# Pallette_v0_5.net
KiCad netlist of a schematic drawn in Altium Designer
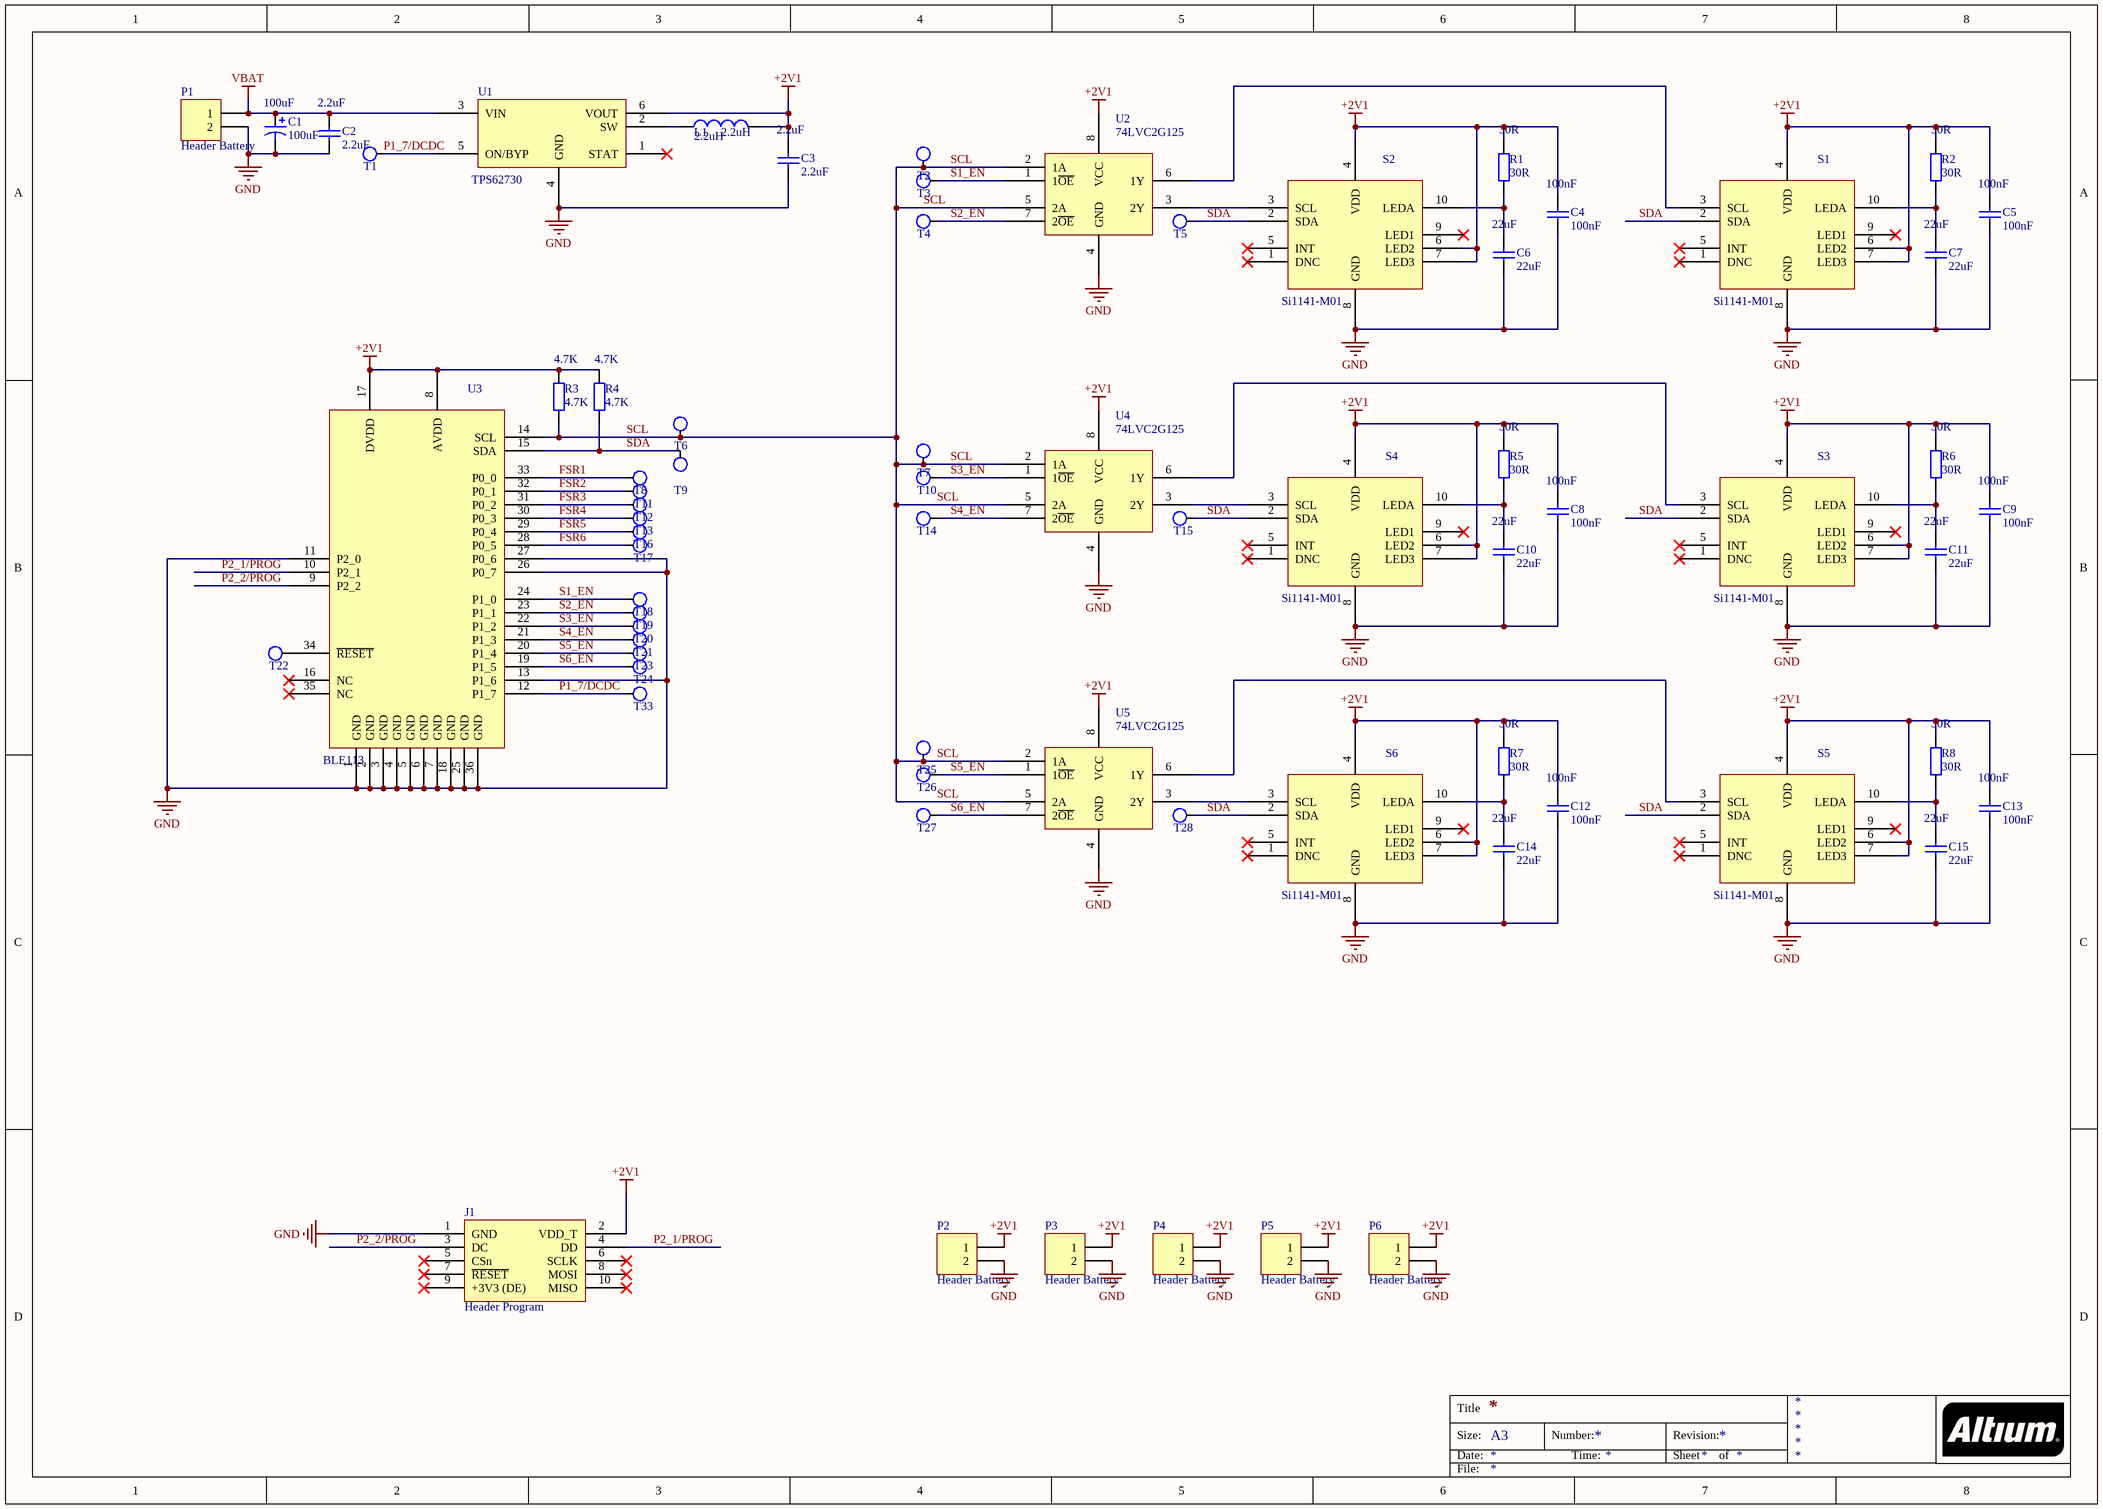
[diagram p0: Pallette v0.5.SchDoc]

(export (version "E")
  (design (tool "Eeschema 10.0.6"))
  (components
    (comp (ref "C1")
      (value "100uF")
      (footprint "1411")
      (description "CAP TANT POLY 100UF 8V 1411")
      (fields
        (field (name "ALTIUM_VALUE") "100uF")
        (field (name "DIGI-KEY PART NUMBER") "P16641CT-ND")
        (field (name "MANUFACTURER") "Panasonic Electronic Components")
      )
      (libsource (lib "Schlib") (part "Cap Pol 100uF"))
    )
    (comp (ref "C2")
      (value "2.2uF")
      (footprint "0402")
      (description "CAP CER 2.2UF 6.3V X5R 0402")
      (fields
        (field (name "ALTIUM_VALUE") "2.2uF")
        (field (name "DIGI-KEY PART NUMBER") "478-7885-1-ND")
        (field (name "MANUFACTURER PART NUMBER") "04026D225KAT2A")
      )
      (libsource (lib "Schlib") (part "Cap 2.2uF"))
    )
    (comp (ref "C3")
      (value "2.2uF")
      (footprint "0402")
      (description "CAP CER 2.2UF 6.3V X5R 0402")
      (fields
        (field (name "ALTIUM_VALUE") "2.2uF")
        (field (name "DIGI-KEY PART NUMBER") "478-7885-1-ND")
        (field (name "MANUFACTURER PART NUMBER") "04026D225KAT2A")
      )
      (libsource (lib "Schlib") (part "Cap 2.2uF"))
    )
    (comp (ref "C4")
      (value "100nF")
      (footprint "0402")
      (description "CAP CER 0.1UF 10V X5R 0402")
      (fields
        (field (name "ALTIUM_VALUE") "100nF")
        (field (name "DIGI-KEY PART NUMBER") "490-1318-1-ND")
        (field (name "MANUFACTURER") "Murata")
      )
      (libsource (lib "Schlib") (part "Cap 100nF"))
    )
    (comp (ref "C5")
      (value "100nF")
      (footprint "0402")
      (description "CAP CER 0.1UF 10V X5R 0402")
      (fields
        (field (name "ALTIUM_VALUE") "100nF")
        (field (name "DIGI-KEY PART NUMBER") "490-1318-1-ND")
        (field (name "MANUFACTURER") "Murata")
      )
      (libsource (lib "Schlib") (part "Cap 100nF"))
    )
    (comp (ref "C6")
      (value "22uF")
      (footprint "0603")
      (description "CAP CER 22UF 6.3V X5R 0603")
      (fields
        (field (name "ALTIUM_VALUE") "22uF")
        (field (name "DIGI-KEY PART NUMBER") "490-7611-1-ND")
        (field (name "MANUFACTURER PART NUMBER") "GRM188R60J226MEA0D")
      )
      (libsource (lib "Schlib") (part "Cap 22uF"))
    )
    (comp (ref "C7")
      (value "22uF")
      (footprint "0603")
      (description "CAP CER 22UF 6.3V X5R 0603")
      (fields
        (field (name "ALTIUM_VALUE") "22uF")
        (field (name "DIGI-KEY PART NUMBER") "490-7611-1-ND")
        (field (name "MANUFACTURER PART NUMBER") "GRM188R60J226MEA0D")
      )
      (libsource (lib "Schlib") (part "Cap 22uF"))
    )
    (comp (ref "C8")
      (value "100nF")
      (footprint "0402")
      (description "CAP CER 0.1UF 10V X5R 0402")
      (fields
        (field (name "ALTIUM_VALUE") "100nF")
        (field (name "DIGI-KEY PART NUMBER") "490-1318-1-ND")
        (field (name "MANUFACTURER") "Murata")
      )
      (libsource (lib "Schlib") (part "Cap 100nF"))
    )
    (comp (ref "C9")
      (value "100nF")
      (footprint "0402")
      (description "CAP CER 0.1UF 10V X5R 0402")
      (fields
        (field (name "ALTIUM_VALUE") "100nF")
        (field (name "DIGI-KEY PART NUMBER") "490-1318-1-ND")
        (field (name "MANUFACTURER") "Murata")
      )
      (libsource (lib "Schlib") (part "Cap 100nF"))
    )
    (comp (ref "C10")
      (value "22uF")
      (footprint "0603")
      (description "CAP CER 22UF 6.3V X5R 0603")
      (fields
        (field (name "ALTIUM_VALUE") "22uF")
        (field (name "DIGI-KEY PART NUMBER") "490-7611-1-ND")
        (field (name "MANUFACTURER PART NUMBER") "GRM188R60J226MEA0D")
      )
      (libsource (lib "Schlib") (part "Cap 22uF"))
    )
    (comp (ref "C11")
      (value "22uF")
      (footprint "0603")
      (description "CAP CER 22UF 6.3V X5R 0603")
      (fields
        (field (name "ALTIUM_VALUE") "22uF")
        (field (name "DIGI-KEY PART NUMBER") "490-7611-1-ND")
        (field (name "MANUFACTURER PART NUMBER") "GRM188R60J226MEA0D")
      )
      (libsource (lib "Schlib") (part "Cap 22uF"))
    )
    (comp (ref "C12")
      (value "100nF")
      (footprint "0402")
      (description "CAP CER 0.1UF 10V X5R 0402")
      (fields
        (field (name "ALTIUM_VALUE") "100nF")
        (field (name "DIGI-KEY PART NUMBER") "490-1318-1-ND")
        (field (name "MANUFACTURER") "Murata")
      )
      (libsource (lib "Schlib") (part "Cap 100nF"))
    )
    (comp (ref "C13")
      (value "100nF")
      (footprint "0402")
      (description "CAP CER 0.1UF 10V X5R 0402")
      (fields
        (field (name "ALTIUM_VALUE") "100nF")
        (field (name "DIGI-KEY PART NUMBER") "490-1318-1-ND")
        (field (name "MANUFACTURER") "Murata")
      )
      (libsource (lib "Schlib") (part "Cap 100nF"))
    )
    (comp (ref "C14")
      (value "22uF")
      (footprint "0603")
      (description "CAP CER 22UF 6.3V X5R 0603")
      (fields
        (field (name "ALTIUM_VALUE") "22uF")
        (field (name "DIGI-KEY PART NUMBER") "490-7611-1-ND")
        (field (name "MANUFACTURER PART NUMBER") "GRM188R60J226MEA0D")
      )
      (libsource (lib "Schlib") (part "Cap 22uF"))
    )
    (comp (ref "C15")
      (value "22uF")
      (footprint "0603")
      (description "CAP CER 22UF 6.3V X5R 0603")
      (fields
        (field (name "ALTIUM_VALUE") "22uF")
        (field (name "DIGI-KEY PART NUMBER") "490-7611-1-ND")
        (field (name "MANUFACTURER PART NUMBER") "GRM188R60J226MEA0D")
      )
      (libsource (lib "Schlib") (part "Cap 22uF"))
    )
    (comp (ref "J1")
      (value "Header Program")
      (footprint "TC2050-IDC-NL")
      (description "PADS PROGRAMMING")
      (libsource (lib "Schlib") (part "Header Program"))
    )
    (comp (ref "L1")
      (value "2.2uH")
      (footprint "0805")
      (description "FIXED IND 2.2UH 800MA 120 MOHM")
      (fields
        (field (name "ALTIUM_VALUE") "2.2uH")
        (field (name "DIGI-KEY PART NUMBER") "445-6758-1-ND")
        (field (name "MANUFACTURER") "TDK Corporation")
      )
      (libsource (lib "Schlib") (part "Ind 2.2uH"))
    )
    (comp (ref "P1")
      (value "Header Battery")
      (footprint "Battery Leads")
      (description "PADS BATTERY")
      (fields (field (name "PUBLISHER") "Altium Limited"))
      (libsource (lib "Schlib") (part "Header Battery"))
    )
    (comp (ref "P2")
      (value "Header Battery")
      (footprint "Battery Leads")
      (description "PADS BATTERY")
      (fields (field (name "PUBLISHER") "Altium Limited"))
      (libsource (lib "Schlib") (part "Header Battery"))
    )
    (comp (ref "P3")
      (value "Header Battery")
      (footprint "Battery Leads")
      (description "PADS BATTERY")
      (fields (field (name "PUBLISHER") "Altium Limited"))
      (libsource (lib "Schlib") (part "Header Battery"))
    )
    (comp (ref "P4")
      (value "Header Battery")
      (footprint "Battery Leads")
      (description "PADS BATTERY")
      (fields (field (name "PUBLISHER") "Altium Limited"))
      (libsource (lib "Schlib") (part "Header Battery"))
    )
    (comp (ref "P5")
      (value "Header Battery")
      (footprint "Battery Leads")
      (description "PADS BATTERY")
      (fields (field (name "PUBLISHER") "Altium Limited"))
      (libsource (lib "Schlib") (part "Header Battery"))
    )
    (comp (ref "P6")
      (value "Header Battery")
      (footprint "Battery Leads")
      (description "PADS BATTERY")
      (fields (field (name "PUBLISHER") "Altium Limited"))
      (libsource (lib "Schlib") (part "Header Battery"))
    )
    (comp (ref "R1")
      (value "30R")
      (footprint "0402")
      (description "RES SMD 30 OHM 1% 1/16W 0402")
      (fields
        (field (name "ALTIUM_VALUE") "30R")
        (field (name "DIGI-KEY PART NUMBER") "311-30LRCT-ND")
        (field (name "MANUFACTURER") "Yageo")
      )
      (libsource (lib "Schlib") (part "Res 30R"))
    )
    (comp (ref "R2")
      (value "30R")
      (footprint "0402")
      (description "RES SMD 30 OHM 1% 1/16W 0402")
      (fields
        (field (name "ALTIUM_VALUE") "30R")
        (field (name "DIGI-KEY PART NUMBER") "311-30LRCT-ND")
        (field (name "MANUFACTURER") "Yageo")
      )
      (libsource (lib "Schlib") (part "Res 30R"))
    )
    (comp (ref "R3")
      (value "4.7K")
      (footprint "0402")
      (description "RES SMD 4.7K OHM 1% 1/16W 0402")
      (fields
        (field (name "ALTIUM_VALUE") "4.7K")
        (field (name "DIGI-KEY PART NUMBER") "311-4.7KLRCT-ND")
        (field (name "MANUFACTURER") "Yageo")
      )
      (libsource (lib "Schlib") (part "Res 4.7K"))
    )
    (comp (ref "R4")
      (value "4.7K")
      (footprint "0402")
      (description "RES SMD 4.7K OHM 1% 1/16W 0402")
      (fields
        (field (name "ALTIUM_VALUE") "4.7K")
        (field (name "DIGI-KEY PART NUMBER") "311-4.7KLRCT-ND")
        (field (name "MANUFACTURER") "Yageo")
      )
      (libsource (lib "Schlib") (part "Res 4.7K"))
    )
    (comp (ref "R5")
      (value "30R")
      (footprint "0402")
      (description "RES SMD 30 OHM 1% 1/16W 0402")
      (fields
        (field (name "ALTIUM_VALUE") "30R")
        (field (name "DIGI-KEY PART NUMBER") "311-30LRCT-ND")
        (field (name "MANUFACTURER") "Yageo")
      )
      (libsource (lib "Schlib") (part "Res 30R"))
    )
    (comp (ref "R6")
      (value "30R")
      (footprint "0402")
      (description "RES SMD 30 OHM 1% 1/16W 0402")
      (fields
        (field (name "ALTIUM_VALUE") "30R")
        (field (name "DIGI-KEY PART NUMBER") "311-30LRCT-ND")
        (field (name "MANUFACTURER") "Yageo")
      )
      (libsource (lib "Schlib") (part "Res 30R"))
    )
    (comp (ref "R7")
      (value "30R")
      (footprint "0402")
      (description "RES SMD 30 OHM 1% 1/16W 0402")
      (fields
        (field (name "ALTIUM_VALUE") "30R")
        (field (name "DIGI-KEY PART NUMBER") "311-30LRCT-ND")
        (field (name "MANUFACTURER") "Yageo")
      )
      (libsource (lib "Schlib") (part "Res 30R"))
    )
    (comp (ref "R8")
      (value "30R")
      (footprint "0402")
      (description "RES SMD 30 OHM 1% 1/16W 0402")
      (fields
        (field (name "ALTIUM_VALUE") "30R")
        (field (name "DIGI-KEY PART NUMBER") "311-30LRCT-ND")
        (field (name "MANUFACTURER") "Yageo")
      )
      (libsource (lib "Schlib") (part "Res 30R"))
    )
    (comp (ref "S1")
      (value "Si1141-M01")
      (footprint "SI1141-M01")
      (description "SENSOR IR PROXIMITY AMB LT 10QFN")
      (fields
        (field (name "DIGI-KEY PART NUMBER") "336-3260-1-ND")
        (field (name "MANUFACTURER") "Silicon Labs")
      )
      (libsource (lib "Schlib") (part "Si1141-M01"))
    )
    (comp (ref "S2")
      (value "Si1141-M01")
      (footprint "SI1141-M01")
      (description "SENSOR IR PROXIMITY AMB LT 10QFN")
      (fields
        (field (name "DIGI-KEY PART NUMBER") "336-3260-1-ND")
        (field (name "MANUFACTURER") "Silicon Labs")
      )
      (libsource (lib "Schlib") (part "Si1141-M01"))
    )
    (comp (ref "S3")
      (value "Si1141-M01")
      (footprint "SI1141-M01")
      (description "SENSOR IR PROXIMITY AMB LT 10QFN")
      (fields
        (field (name "DIGI-KEY PART NUMBER") "336-3260-1-ND")
        (field (name "MANUFACTURER") "Silicon Labs")
      )
      (libsource (lib "Schlib") (part "Si1141-M01"))
    )
    (comp (ref "S4")
      (value "Si1141-M01")
      (footprint "SI1141-M01")
      (description "SENSOR IR PROXIMITY AMB LT 10QFN")
      (fields
        (field (name "DIGI-KEY PART NUMBER") "336-3260-1-ND")
        (field (name "MANUFACTURER") "Silicon Labs")
      )
      (libsource (lib "Schlib") (part "Si1141-M01"))
    )
    (comp (ref "S5")
      (value "Si1141-M01")
      (footprint "SI1141-M01")
      (description "SENSOR IR PROXIMITY AMB LT 10QFN")
      (fields
        (field (name "DIGI-KEY PART NUMBER") "336-3260-1-ND")
        (field (name "MANUFACTURER") "Silicon Labs")
      )
      (libsource (lib "Schlib") (part "Si1141-M01"))
    )
    (comp (ref "S6")
      (value "Si1141-M01")
      (footprint "SI1141-M01")
      (description "SENSOR IR PROXIMITY AMB LT 10QFN")
      (fields
        (field (name "DIGI-KEY PART NUMBER") "336-3260-1-ND")
        (field (name "MANUFACTURER") "Silicon Labs")
      )
      (libsource (lib "Schlib") (part "Si1141-M01"))
    )
    (comp (ref "T1")
      (value "TP 1.2X2MM")
      (footprint "TP 1.2x2MM")
      (description "TEST POINT")
      (libsource (lib "Schlib") (part "TP 1.2X2MM"))
    )
    (comp (ref "T2")
      (value "TP 1.2X2MM")
      (footprint "TP 1.2x2MM")
      (description "TEST POINT")
      (libsource (lib "Schlib") (part "TP 1.2X2MM"))
    )
    (comp (ref "T3")
      (value "TP 1.2X2MM")
      (footprint "TP 1.2x2MM")
      (description "TEST POINT")
      (libsource (lib "Schlib") (part "TP 1.2X2MM"))
    )
    (comp (ref "T4")
      (value "TP 1.2X2MM")
      (footprint "TP 1.2x2MM")
      (description "TEST POINT")
      (libsource (lib "Schlib") (part "TP 1.2X2MM"))
    )
    (comp (ref "T5")
      (value "TP 1.2X2MM")
      (footprint "TP 1.2x2MM")
      (description "TEST POINT")
      (libsource (lib "Schlib") (part "TP 1.2X2MM"))
    )
    (comp (ref "T6")
      (value "TP 1.2X2MM")
      (footprint "TP 1.2x2MM")
      (description "TEST POINT")
      (libsource (lib "Schlib") (part "TP 1.2X2MM"))
    )
    (comp (ref "T7")
      (value "TP 1.2X2MM")
      (footprint "TP 1.2x2MM")
      (description "TEST POINT")
      (libsource (lib "Schlib") (part "TP 1.2X2MM"))
    )
    (comp (ref "T8")
      (value "TP 1.2X2MM")
      (footprint "TP 1.2x2MM")
      (description "TEST POINT")
      (libsource (lib "Schlib") (part "TP 1.2X2MM"))
    )
    (comp (ref "T9")
      (value "TP 1.2X2MM")
      (footprint "TP 1.2x2MM")
      (description "TEST POINT")
      (libsource (lib "Schlib") (part "TP 1.2X2MM"))
    )
    (comp (ref "T10")
      (value "TP 1.2X2MM")
      (footprint "TP 1.2x2MM")
      (description "TEST POINT")
      (libsource (lib "Schlib") (part "TP 1.2X2MM"))
    )
    (comp (ref "T11")
      (value "TP 1.2X2MM")
      (footprint "TP 1.2x2MM")
      (description "TEST POINT")
      (libsource (lib "Schlib") (part "TP 1.2X2MM"))
    )
    (comp (ref "T12")
      (value "TP 1.2X2MM")
      (footprint "TP 1.2x2MM")
      (description "TEST POINT")
      (libsource (lib "Schlib") (part "TP 1.2X2MM"))
    )
    (comp (ref "T13")
      (value "TP 1.2X2MM")
      (footprint "TP 1.2x2MM")
      (description "TEST POINT")
      (libsource (lib "Schlib") (part "TP 1.2X2MM"))
    )
    (comp (ref "T14")
      (value "TP 1.2X2MM")
      (footprint "TP 1.2x2MM")
      (description "TEST POINT")
      (libsource (lib "Schlib") (part "TP 1.2X2MM"))
    )
    (comp (ref "T15")
      (value "TP 1.2X2MM")
      (footprint "TP 1.2x2MM")
      (description "TEST POINT")
      (libsource (lib "Schlib") (part "TP 1.2X2MM"))
    )
    (comp (ref "T16")
      (value "TP 1.2X2MM")
      (footprint "TP 1.2x2MM")
      (description "TEST POINT")
      (libsource (lib "Schlib") (part "TP 1.2X2MM"))
    )
    (comp (ref "T17")
      (value "TP 1.2X2MM")
      (footprint "TP 1.2x2MM")
      (description "TEST POINT")
      (libsource (lib "Schlib") (part "TP 1.2X2MM"))
    )
    (comp (ref "T18")
      (value "TP 1.2X2MM")
      (footprint "TP 1.2x2MM")
      (description "TEST POINT")
      (libsource (lib "Schlib") (part "TP 1.2X2MM"))
    )
    (comp (ref "T19")
      (value "TP 1.2X2MM")
      (footprint "TP 1.2x2MM")
      (description "TEST POINT")
      (libsource (lib "Schlib") (part "TP 1.2X2MM"))
    )
    (comp (ref "T20")
      (value "TP 1.2X2MM")
      (footprint "TP 1.2x2MM")
      (description "TEST POINT")
      (libsource (lib "Schlib") (part "TP 1.2X2MM"))
    )
    (comp (ref "T21")
      (value "TP 1.2X2MM")
      (footprint "TP 1.2x2MM")
      (description "TEST POINT")
      (libsource (lib "Schlib") (part "TP 1.2X2MM"))
    )
    (comp (ref "T22")
      (value "TP 1.2X2MM")
      (footprint "TP 1.2x2MM")
      (description "TEST POINT")
      (libsource (lib "Schlib") (part "TP 1.2X2MM"))
    )
    (comp (ref "T23")
      (value "TP 1.2X2MM")
      (footprint "TP 1.2x2MM")
      (description "TEST POINT")
      (libsource (lib "Schlib") (part "TP 1.2X2MM"))
    )
    (comp (ref "T24")
      (value "TP 1.2X2MM")
      (footprint "TP 1.2x2MM")
      (description "TEST POINT")
      (libsource (lib "Schlib") (part "TP 1.2X2MM"))
    )
    (comp (ref "T25")
      (value "TP 1.2X2MM")
      (footprint "TP 1.2x2MM")
      (description "TEST POINT")
      (libsource (lib "Schlib") (part "TP 1.2X2MM"))
    )
    (comp (ref "T26")
      (value "TP 1.2X2MM")
      (footprint "TP 1.2x2MM")
      (description "TEST POINT")
      (libsource (lib "Schlib") (part "TP 1.2X2MM"))
    )
    (comp (ref "T27")
      (value "TP 1.2X2MM")
      (footprint "TP 1.2x2MM")
      (description "TEST POINT")
      (libsource (lib "Schlib") (part "TP 1.2X2MM"))
    )
    (comp (ref "T28")
      (value "TP 1.2X2MM")
      (footprint "TP 1.2x2MM")
      (description "TEST POINT")
      (libsource (lib "Schlib") (part "TP 1.2X2MM"))
    )
    (comp (ref "T33")
      (value "TP 1.2X2MM")
      (footprint "TP 1.2x2MM")
      (description "TEST POINT")
      (libsource (lib "Schlib") (part "TP 1.2X2MM"))
    )
    (comp (ref "U1")
      (value "TPS62730")
      (footprint "6-UFDFN")
      (description "IC DCDC CONV STP-DN SYNC LP 6SON")
      (fields
        (field (name "DIGI-KEY PART NUMBER") "296-28820-1-ND")
        (field (name "MANUFACTURER") "Texas Instruments")
      )
      (libsource (lib "Schlib") (part "TPS62730"))
    )
    (comp (ref "U2")
      (value "74LVC2G125")
      (footprint "VSSOP8")
      (description "IC BUS BUFF DVR TRI-ST DL 8VSSOP")
      (fields
        (field (name "MANUFACTURER") "NXP Semiconductors")
        (field (name "MANUFACTURER PART NUMBER") "74LVC2G125DC,125")
      )
      (libsource (lib "Schlib") (part "74LVC2G125"))
    )
    (comp (ref "U3")
      (value "BLE113")
      (footprint "BLE113-A")
      (description "MODULE BT 4.0 BLE113 OTA")
      (fields
        (field (name "MANUFACTURER") "Silicon Labs")
        (field (name "MANUFACTURER PART NUMBER") "BLE113-A-M256K")
      )
      (libsource (lib "Schlib") (part "BLE113"))
    )
    (comp (ref "U4")
      (value "74LVC2G125")
      (footprint "VSSOP8")
      (description "IC BUS BUFF DVR TRI-ST DL 8VSSOP")
      (fields
        (field (name "MANUFACTURER") "NXP Semiconductors")
        (field (name "MANUFACTURER PART NUMBER") "74LVC2G125DC,125")
      )
      (libsource (lib "Schlib") (part "74LVC2G125"))
    )
    (comp (ref "U5")
      (value "74LVC2G125")
      (footprint "VSSOP8")
      (description "IC BUS BUFF DVR TRI-ST DL 8VSSOP")
      (fields
        (field (name "MANUFACTURER") "NXP Semiconductors")
        (field (name "MANUFACTURER PART NUMBER") "74LVC2G125DC,125")
      )
      (libsource (lib "Schlib") (part "74LVC2G125"))
    )
  )
  (nets
    (net (code "1") (name "+2V1") (class "Default")
      (node (ref "C12") (pin "2") (pinfunction "2_2") (pintype "passive"))
      (node (ref "C13") (pin "2") (pinfunction "2_2") (pintype "passive"))
      (node (ref "C3") (pin "2") (pinfunction "2_2") (pintype "passive"))
      (node (ref "C4") (pin "2") (pinfunction "2_2") (pintype "passive"))
      (node (ref "C5") (pin "2") (pinfunction "2_2") (pintype "passive"))
      (node (ref "C8") (pin "2") (pinfunction "2_2") (pintype "passive"))
      (node (ref "C9") (pin "2") (pinfunction "2_2") (pintype "passive"))
      (node (ref "J1") (pin "2") (pinfunction "VDD_T_2") (pintype "passive"))
      (node (ref "L1") (pin "2") (pinfunction "2_2") (pintype "passive"))
      (node (ref "P2") (pin "1") (pinfunction "1_1") (pintype "passive"))
      (node (ref "P3") (pin "1") (pinfunction "1_1") (pintype "passive"))
      (node (ref "P4") (pin "1") (pinfunction "1_1") (pintype "passive"))
      (node (ref "P5") (pin "1") (pinfunction "1_1") (pintype "passive"))
      (node (ref "P6") (pin "1") (pinfunction "1_1") (pintype "passive"))
      (node (ref "R1") (pin "2") (pinfunction "2_2") (pintype "passive"))
      (node (ref "R2") (pin "2") (pinfunction "2_2") (pintype "passive"))
      (node (ref "R3") (pin "2") (pinfunction "2_2") (pintype "passive"))
      (node (ref "R4") (pin "2") (pinfunction "2_2") (pintype "passive"))
      (node (ref "R5") (pin "2") (pinfunction "2_2") (pintype "passive"))
      (node (ref "R6") (pin "2") (pinfunction "2_2") (pintype "passive"))
      (node (ref "R7") (pin "2") (pinfunction "2_2") (pintype "passive"))
      (node (ref "R8") (pin "2") (pinfunction "2_2") (pintype "passive"))
      (node (ref "S1") (pin "4") (pinfunction "VDD_4") (pintype "passive"))
      (node (ref "S1") (pin "6") (pinfunction "LED2_6") (pintype "passive"))
      (node (ref "S1") (pin "7") (pinfunction "LED3_7") (pintype "passive"))
      (node (ref "S2") (pin "4") (pinfunction "VDD_4") (pintype "passive"))
      (node (ref "S2") (pin "6") (pinfunction "LED2_6") (pintype "passive"))
      (node (ref "S2") (pin "7") (pinfunction "LED3_7") (pintype "passive"))
      (node (ref "S3") (pin "4") (pinfunction "VDD_4") (pintype "passive"))
      (node (ref "S3") (pin "6") (pinfunction "LED2_6") (pintype "passive"))
      (node (ref "S3") (pin "7") (pinfunction "LED3_7") (pintype "passive"))
      (node (ref "S4") (pin "4") (pinfunction "VDD_4") (pintype "passive"))
      (node (ref "S4") (pin "6") (pinfunction "LED2_6") (pintype "passive"))
      (node (ref "S4") (pin "7") (pinfunction "LED3_7") (pintype "passive"))
      (node (ref "S5") (pin "4") (pinfunction "VDD_4") (pintype "passive"))
      (node (ref "S5") (pin "6") (pinfunction "LED2_6") (pintype "passive"))
      (node (ref "S5") (pin "7") (pinfunction "LED3_7") (pintype "passive"))
      (node (ref "S6") (pin "4") (pinfunction "VDD_4") (pintype "passive"))
      (node (ref "S6") (pin "6") (pinfunction "LED2_6") (pintype "passive"))
      (node (ref "S6") (pin "7") (pinfunction "LED3_7") (pintype "passive"))
      (node (ref "U1") (pin "6") (pinfunction "VOUT_6") (pintype "passive"))
      (node (ref "U2") (pin "8") (pinfunction "VCC_8") (pintype "passive"))
      (node (ref "U3") (pin "17") (pinfunction "DVDD_17") (pintype "passive"))
      (node (ref "U3") (pin "8") (pinfunction "AVDD_8") (pintype "passive"))
      (node (ref "U4") (pin "8") (pinfunction "VCC_8") (pintype "passive"))
      (node (ref "U5") (pin "8") (pinfunction "VCC_8") (pintype "passive"))
    )
    (net (code "2") (name "/FSR1") (class "Default")
      (node (ref "T8") (pin "1") (pintype "passive"))
      (node (ref "U3") (pin "33") (pinfunction "P0_0_33") (pintype "passive"))
    )
    (net (code "3") (name "/FSR2") (class "Default")
      (node (ref "T11") (pin "1") (pintype "passive"))
      (node (ref "U3") (pin "32") (pinfunction "P0_1_32") (pintype "passive"))
    )
    (net (code "4") (name "/FSR3") (class "Default")
      (node (ref "T12") (pin "1") (pintype "passive"))
      (node (ref "U3") (pin "31") (pinfunction "P0_2_31") (pintype "passive"))
    )
    (net (code "5") (name "/FSR4") (class "Default")
      (node (ref "T13") (pin "1") (pintype "passive"))
      (node (ref "U3") (pin "30") (pinfunction "P0_3_30") (pintype "passive"))
    )
    (net (code "6") (name "/FSR5") (class "Default")
      (node (ref "T16") (pin "1") (pintype "passive"))
      (node (ref "U3") (pin "29") (pinfunction "P0_4_29") (pintype "passive"))
    )
    (net (code "7") (name "/FSR6") (class "Default")
      (node (ref "T17") (pin "1") (pintype "passive"))
      (node (ref "U3") (pin "28") (pinfunction "P0_5_28") (pintype "passive"))
    )
    (net (code "8") (name "/P1_7{slash}DCDC") (class "Default")
      (node (ref "T1") (pin "1") (pintype "passive"))
      (node (ref "T33") (pin "1") (pintype "passive"))
      (node (ref "U1") (pin "5") (pinfunction "ON/BYP_5") (pintype "passive"))
      (node (ref "U3") (pin "12") (pinfunction "P1_7_12") (pintype "passive"))
    )
    (net (code "9") (name "/P2_1{slash}PROG") (class "Default")
      (node (ref "J1") (pin "4") (pinfunction "DD_4") (pintype "passive"))
      (node (ref "U3") (pin "10") (pinfunction "P2_1_10") (pintype "passive"))
    )
    (net (code "10") (name "/P2_2{slash}PROG") (class "Default")
      (node (ref "J1") (pin "3") (pinfunction "DC_3") (pintype "passive"))
      (node (ref "U3") (pin "9") (pinfunction "P2_2_9") (pintype "passive"))
    )
    (net (code "11") (name "/S1_EN") (class "Default")
      (node (ref "T18") (pin "1") (pintype "passive"))
      (node (ref "T3") (pin "1") (pintype "passive"))
      (node (ref "U2") (pin "1") (pinfunction "1~{OE}_1") (pintype "passive"))
      (node (ref "U3") (pin "24") (pinfunction "P1_0_24") (pintype "passive"))
    )
    (net (code "12") (name "/S2_EN") (class "Default")
      (node (ref "T19") (pin "1") (pintype "passive"))
      (node (ref "T4") (pin "1") (pintype "passive"))
      (node (ref "U2") (pin "7") (pinfunction "2~{OE}_7") (pintype "passive"))
      (node (ref "U3") (pin "23") (pinfunction "P1_1_23") (pintype "passive"))
    )
    (net (code "13") (name "/S3_EN") (class "Default")
      (node (ref "T10") (pin "1") (pintype "passive"))
      (node (ref "T20") (pin "1") (pintype "passive"))
      (node (ref "U3") (pin "22") (pinfunction "P1_2_22") (pintype "passive"))
      (node (ref "U4") (pin "1") (pinfunction "1~{OE}_1") (pintype "passive"))
    )
    (net (code "14") (name "/S4_EN") (class "Default")
      (node (ref "T14") (pin "1") (pintype "passive"))
      (node (ref "T21") (pin "1") (pintype "passive"))
      (node (ref "U3") (pin "21") (pinfunction "P1_3_21") (pintype "passive"))
      (node (ref "U4") (pin "7") (pinfunction "2~{OE}_7") (pintype "passive"))
    )
    (net (code "15") (name "/S5_EN") (class "Default")
      (node (ref "T23") (pin "1") (pintype "passive"))
      (node (ref "T26") (pin "1") (pintype "passive"))
      (node (ref "U3") (pin "20") (pinfunction "P1_4_20") (pintype "passive"))
      (node (ref "U5") (pin "1") (pinfunction "1~{OE}_1") (pintype "passive"))
    )
    (net (code "16") (name "/S6_EN") (class "Default")
      (node (ref "T24") (pin "1") (pintype "passive"))
      (node (ref "T27") (pin "1") (pintype "passive"))
      (node (ref "U3") (pin "19") (pinfunction "P1_5_19") (pintype "passive"))
      (node (ref "U5") (pin "7") (pinfunction "2~{OE}_7") (pintype "passive"))
    )
    (net (code "17") (name "/SCL") (class "Default")
      (node (ref "R3") (pin "1") (pinfunction "1_1") (pintype "passive"))
      (node (ref "T2") (pin "1") (pintype "passive"))
      (node (ref "T25") (pin "1") (pintype "passive"))
      (node (ref "T6") (pin "1") (pintype "passive"))
      (node (ref "T7") (pin "1") (pintype "passive"))
      (node (ref "U2") (pin "2") (pinfunction "1A_2") (pintype "passive"))
      (node (ref "U2") (pin "5") (pinfunction "2A_5") (pintype "passive"))
      (node (ref "U3") (pin "14") (pinfunction "SCL_14") (pintype "passive"))
      (node (ref "U4") (pin "2") (pinfunction "1A_2") (pintype "passive"))
      (node (ref "U4") (pin "5") (pinfunction "2A_5") (pintype "passive"))
      (node (ref "U5") (pin "2") (pinfunction "1A_2") (pintype "passive"))
      (node (ref "U5") (pin "5") (pinfunction "2A_5") (pintype "passive"))
    )
    (net (code "18") (name "/SDA") (class "Default")
      (node (ref "R4") (pin "1") (pinfunction "1_1") (pintype "passive"))
      (node (ref "S1") (pin "2") (pinfunction "SDA_2") (pintype "passive"))
      (node (ref "S2") (pin "2") (pinfunction "SDA_2") (pintype "passive"))
      (node (ref "S3") (pin "2") (pinfunction "SDA_2") (pintype "passive"))
      (node (ref "S4") (pin "2") (pinfunction "SDA_2") (pintype "passive"))
      (node (ref "S5") (pin "2") (pinfunction "SDA_2") (pintype "passive"))
      (node (ref "S6") (pin "2") (pinfunction "SDA_2") (pintype "passive"))
      (node (ref "T15") (pin "1") (pintype "passive"))
      (node (ref "T28") (pin "1") (pintype "passive"))
      (node (ref "T5") (pin "1") (pintype "passive"))
      (node (ref "T9") (pin "1") (pintype "passive"))
      (node (ref "U3") (pin "15") (pinfunction "SDA_15") (pintype "passive"))
    )
    (net (code "19") (name "GND") (class "Default")
      (node (ref "C1") (pin "2") (pinfunction "2_2") (pintype "passive"))
      (node (ref "C10") (pin "1") (pinfunction "1_1") (pintype "passive"))
      (node (ref "C11") (pin "1") (pinfunction "1_1") (pintype "passive"))
      (node (ref "C12") (pin "1") (pinfunction "1_1") (pintype "passive"))
      (node (ref "C13") (pin "1") (pinfunction "1_1") (pintype "passive"))
      (node (ref "C14") (pin "1") (pinfunction "1_1") (pintype "passive"))
      (node (ref "C15") (pin "1") (pinfunction "1_1") (pintype "passive"))
      (node (ref "C2") (pin "1") (pinfunction "1_1") (pintype "passive"))
      (node (ref "C3") (pin "1") (pinfunction "1_1") (pintype "passive"))
      (node (ref "C4") (pin "1") (pinfunction "1_1") (pintype "passive"))
      (node (ref "C5") (pin "1") (pinfunction "1_1") (pintype "passive"))
      (node (ref "C6") (pin "1") (pinfunction "1_1") (pintype "passive"))
      (node (ref "C7") (pin "1") (pinfunction "1_1") (pintype "passive"))
      (node (ref "C8") (pin "1") (pinfunction "1_1") (pintype "passive"))
      (node (ref "C9") (pin "1") (pinfunction "1_1") (pintype "passive"))
      (node (ref "J1") (pin "1") (pinfunction "GND_1") (pintype "passive"))
      (node (ref "P1") (pin "2") (pinfunction "2_2") (pintype "passive"))
      (node (ref "P2") (pin "2") (pinfunction "2_2") (pintype "passive"))
      (node (ref "P3") (pin "2") (pinfunction "2_2") (pintype "passive"))
      (node (ref "P4") (pin "2") (pinfunction "2_2") (pintype "passive"))
      (node (ref "P5") (pin "2") (pinfunction "2_2") (pintype "passive"))
      (node (ref "P6") (pin "2") (pinfunction "2_2") (pintype "passive"))
      (node (ref "S1") (pin "8") (pinfunction "GND_8") (pintype "passive"))
      (node (ref "S2") (pin "8") (pinfunction "GND_8") (pintype "passive"))
      (node (ref "S3") (pin "8") (pinfunction "GND_8") (pintype "passive"))
      (node (ref "S4") (pin "8") (pinfunction "GND_8") (pintype "passive"))
      (node (ref "S5") (pin "8") (pinfunction "GND_8") (pintype "passive"))
      (node (ref "S6") (pin "8") (pinfunction "GND_8") (pintype "passive"))
      (node (ref "U1") (pin "4") (pinfunction "GND_4") (pintype "passive"))
      (node (ref "U2") (pin "4") (pinfunction "GND_4") (pintype "passive"))
      (node (ref "U3") (pin "1") (pinfunction "GND_1") (pintype "passive"))
      (node (ref "U3") (pin "11") (pinfunction "P2_0_11") (pintype "passive"))
      (node (ref "U3") (pin "13") (pinfunction "P1_6_13") (pintype "passive"))
      (node (ref "U3") (pin "18") (pinfunction "GND_18") (pintype "passive"))
      (node (ref "U3") (pin "2") (pinfunction "GND_2") (pintype "passive"))
      (node (ref "U3") (pin "25") (pinfunction "GND_25") (pintype "passive"))
      (node (ref "U3") (pin "26") (pinfunction "P0_7_26") (pintype "passive"))
      (node (ref "U3") (pin "27") (pinfunction "P0_6_27") (pintype "passive"))
      (node (ref "U3") (pin "3") (pinfunction "GND_3") (pintype "passive"))
      (node (ref "U3") (pin "36") (pinfunction "GND_36") (pintype "passive"))
      (node (ref "U3") (pin "4") (pinfunction "GND_4") (pintype "passive"))
      (node (ref "U3") (pin "5") (pinfunction "GND_5") (pintype "passive"))
      (node (ref "U3") (pin "6") (pinfunction "GND_6") (pintype "passive"))
      (node (ref "U3") (pin "7") (pinfunction "GND_7") (pintype "passive"))
      (node (ref "U4") (pin "4") (pinfunction "GND_4") (pintype "passive"))
      (node (ref "U5") (pin "4") (pinfunction "GND_4") (pintype "passive"))
    )
    (net (code "20") (name "Net-(S1-LEDA)") (class "Default")
      (node (ref "C7") (pin "2") (pinfunction "2_2") (pintype "passive"))
      (node (ref "R2") (pin "1") (pinfunction "1_1") (pintype "passive"))
      (node (ref "S1") (pin "10") (pinfunction "LEDA_10") (pintype "passive"))
    )
    (net (code "21") (name "Net-(S1-SCL)") (class "Default")
      (node (ref "S1") (pin "3") (pinfunction "SCL_3") (pintype "passive"))
      (node (ref "U2") (pin "6") (pinfunction "1Y_6") (pintype "passive"))
    )
    (net (code "22") (name "Net-(S2-LEDA)") (class "Default")
      (node (ref "C6") (pin "2") (pinfunction "2_2") (pintype "passive"))
      (node (ref "R1") (pin "1") (pinfunction "1_1") (pintype "passive"))
      (node (ref "S2") (pin "10") (pinfunction "LEDA_10") (pintype "passive"))
    )
    (net (code "23") (name "Net-(S2-SCL)") (class "Default")
      (node (ref "S2") (pin "3") (pinfunction "SCL_3") (pintype "passive"))
      (node (ref "U2") (pin "3") (pinfunction "2Y_3") (pintype "passive"))
    )
    (net (code "24") (name "Net-(S3-LEDA)") (class "Default")
      (node (ref "C11") (pin "2") (pinfunction "2_2") (pintype "passive"))
      (node (ref "R6") (pin "1") (pinfunction "1_1") (pintype "passive"))
      (node (ref "S3") (pin "10") (pinfunction "LEDA_10") (pintype "passive"))
    )
    (net (code "25") (name "Net-(S3-SCL)") (class "Default")
      (node (ref "S3") (pin "3") (pinfunction "SCL_3") (pintype "passive"))
      (node (ref "U4") (pin "6") (pinfunction "1Y_6") (pintype "passive"))
    )
    (net (code "26") (name "Net-(S4-LEDA)") (class "Default")
      (node (ref "C10") (pin "2") (pinfunction "2_2") (pintype "passive"))
      (node (ref "R5") (pin "1") (pinfunction "1_1") (pintype "passive"))
      (node (ref "S4") (pin "10") (pinfunction "LEDA_10") (pintype "passive"))
    )
    (net (code "27") (name "Net-(S4-SCL)") (class "Default")
      (node (ref "S4") (pin "3") (pinfunction "SCL_3") (pintype "passive"))
      (node (ref "U4") (pin "3") (pinfunction "2Y_3") (pintype "passive"))
    )
    (net (code "28") (name "Net-(S5-LEDA)") (class "Default")
      (node (ref "C15") (pin "2") (pinfunction "2_2") (pintype "passive"))
      (node (ref "R8") (pin "1") (pinfunction "1_1") (pintype "passive"))
      (node (ref "S5") (pin "10") (pinfunction "LEDA_10") (pintype "passive"))
    )
    (net (code "29") (name "Net-(S5-SCL)") (class "Default")
      (node (ref "S5") (pin "3") (pinfunction "SCL_3") (pintype "passive"))
      (node (ref "U5") (pin "6") (pinfunction "1Y_6") (pintype "passive"))
    )
    (net (code "30") (name "Net-(S6-LEDA)") (class "Default")
      (node (ref "C14") (pin "2") (pinfunction "2_2") (pintype "passive"))
      (node (ref "R7") (pin "1") (pinfunction "1_1") (pintype "passive"))
      (node (ref "S6") (pin "10") (pinfunction "LEDA_10") (pintype "passive"))
    )
    (net (code "31") (name "Net-(S6-SCL)") (class "Default")
      (node (ref "S6") (pin "3") (pinfunction "SCL_3") (pintype "passive"))
      (node (ref "U5") (pin "3") (pinfunction "2Y_3") (pintype "passive"))
    )
    (net (code "32") (name "Net-(U1-SW)") (class "Default")
      (node (ref "L1") (pin "1") (pinfunction "1_1") (pintype "passive"))
      (node (ref "U1") (pin "2") (pinfunction "SW_2") (pintype "passive"))
    )
    (net (code "33") (name "Net-(U3-~{RESET})") (class "Default")
      (node (ref "T22") (pin "1") (pintype "passive"))
      (node (ref "U3") (pin "34") (pinfunction "~{RESET}_34") (pintype "passive"))
    )
    (net (code "34") (name "VBAT") (class "Default")
      (node (ref "C1") (pin "1") (pinfunction "1_1") (pintype "passive"))
      (node (ref "C2") (pin "2") (pinfunction "2_2") (pintype "passive"))
      (node (ref "P1") (pin "1") (pinfunction "1_1") (pintype "passive"))
      (node (ref "U1") (pin "3") (pinfunction "VIN_3") (pintype "passive"))
    )
    (net (code "35") (name "unconnected-(J1-+3V3_(DE)-Pad9)") (class "Default")
      (node (ref "J1") (pin "9") (pinfunction "+3V3_(DE)_9") (pintype "passive+no_connect"))
    )
    (net (code "36") (name "unconnected-(J1-CSn-Pad5)") (class "Default")
      (node (ref "J1") (pin "5") (pinfunction "CSn_5") (pintype "passive+no_connect"))
    )
    (net (code "37") (name "unconnected-(J1-MISO-Pad10)") (class "Default")
      (node (ref "J1") (pin "10") (pinfunction "MISO_10") (pintype "passive+no_connect"))
    )
    (net (code "38") (name "unconnected-(J1-MOSI-Pad8)") (class "Default")
      (node (ref "J1") (pin "8") (pinfunction "MOSI_8") (pintype "passive+no_connect"))
    )
    (net (code "39") (name "unconnected-(J1-SCLK-Pad6)") (class "Default")
      (node (ref "J1") (pin "6") (pinfunction "SCLK_6") (pintype "passive+no_connect"))
    )
    (net (code "40") (name "unconnected-(J1-~{RESET}-Pad7)") (class "Default")
      (node (ref "J1") (pin "7") (pinfunction "~{RESET}_7") (pintype "passive+no_connect"))
    )
    (net (code "41") (name "unconnected-(S1-DNC-Pad1)") (class "Default")
      (node (ref "S1") (pin "1") (pinfunction "DNC_1") (pintype "passive+no_connect"))
    )
    (net (code "42") (name "unconnected-(S1-INT-Pad5)") (class "Default")
      (node (ref "S1") (pin "5") (pinfunction "INT_5") (pintype "passive+no_connect"))
    )
    (net (code "43") (name "unconnected-(S1-LED1-Pad9)") (class "Default")
      (node (ref "S1") (pin "9") (pinfunction "LED1_9") (pintype "passive+no_connect"))
    )
    (net (code "44") (name "unconnected-(S2-DNC-Pad1)") (class "Default")
      (node (ref "S2") (pin "1") (pinfunction "DNC_1") (pintype "passive+no_connect"))
    )
    (net (code "45") (name "unconnected-(S2-INT-Pad5)") (class "Default")
      (node (ref "S2") (pin "5") (pinfunction "INT_5") (pintype "passive+no_connect"))
    )
    (net (code "46") (name "unconnected-(S2-LED1-Pad9)") (class "Default")
      (node (ref "S2") (pin "9") (pinfunction "LED1_9") (pintype "passive+no_connect"))
    )
    (net (code "47") (name "unconnected-(S3-DNC-Pad1)") (class "Default")
      (node (ref "S3") (pin "1") (pinfunction "DNC_1") (pintype "passive+no_connect"))
    )
    (net (code "48") (name "unconnected-(S3-INT-Pad5)") (class "Default")
      (node (ref "S3") (pin "5") (pinfunction "INT_5") (pintype "passive+no_connect"))
    )
    (net (code "49") (name "unconnected-(S3-LED1-Pad9)") (class "Default")
      (node (ref "S3") (pin "9") (pinfunction "LED1_9") (pintype "passive+no_connect"))
    )
    (net (code "50") (name "unconnected-(S4-DNC-Pad1)") (class "Default")
      (node (ref "S4") (pin "1") (pinfunction "DNC_1") (pintype "passive+no_connect"))
    )
    (net (code "51") (name "unconnected-(S4-INT-Pad5)") (class "Default")
      (node (ref "S4") (pin "5") (pinfunction "INT_5") (pintype "passive+no_connect"))
    )
    (net (code "52") (name "unconnected-(S4-LED1-Pad9)") (class "Default")
      (node (ref "S4") (pin "9") (pinfunction "LED1_9") (pintype "passive+no_connect"))
    )
    (net (code "53") (name "unconnected-(S5-DNC-Pad1)") (class "Default")
      (node (ref "S5") (pin "1") (pinfunction "DNC_1") (pintype "passive+no_connect"))
    )
    (net (code "54") (name "unconnected-(S5-INT-Pad5)") (class "Default")
      (node (ref "S5") (pin "5") (pinfunction "INT_5") (pintype "passive+no_connect"))
    )
    (net (code "55") (name "unconnected-(S5-LED1-Pad9)") (class "Default")
      (node (ref "S5") (pin "9") (pinfunction "LED1_9") (pintype "passive+no_connect"))
    )
    (net (code "56") (name "unconnected-(S6-DNC-Pad1)") (class "Default")
      (node (ref "S6") (pin "1") (pinfunction "DNC_1") (pintype "passive+no_connect"))
    )
    (net (code "57") (name "unconnected-(S6-INT-Pad5)") (class "Default")
      (node (ref "S6") (pin "5") (pinfunction "INT_5") (pintype "passive+no_connect"))
    )
    (net (code "58") (name "unconnected-(S6-LED1-Pad9)") (class "Default")
      (node (ref "S6") (pin "9") (pinfunction "LED1_9") (pintype "passive+no_connect"))
    )
    (net (code "59") (name "unconnected-(U1-STAT-Pad1)") (class "Default")
      (node (ref "U1") (pin "1") (pinfunction "STAT_1") (pintype "passive+no_connect"))
    )
    (net (code "60") (name "unconnected-(U3-NC-Pad16)") (class "Default")
      (node (ref "U3") (pin "16") (pinfunction "NC_16") (pintype "passive+no_connect"))
    )
    (net (code "61") (name "unconnected-(U3-NC-Pad35)") (class "Default")
      (node (ref "U3") (pin "35") (pinfunction "NC_35") (pintype "passive+no_connect"))
    )
  )
)
